# Esquem_tico_TP1_ASSD.net
KiCad netlist of a schematic drawn in Altium Designer
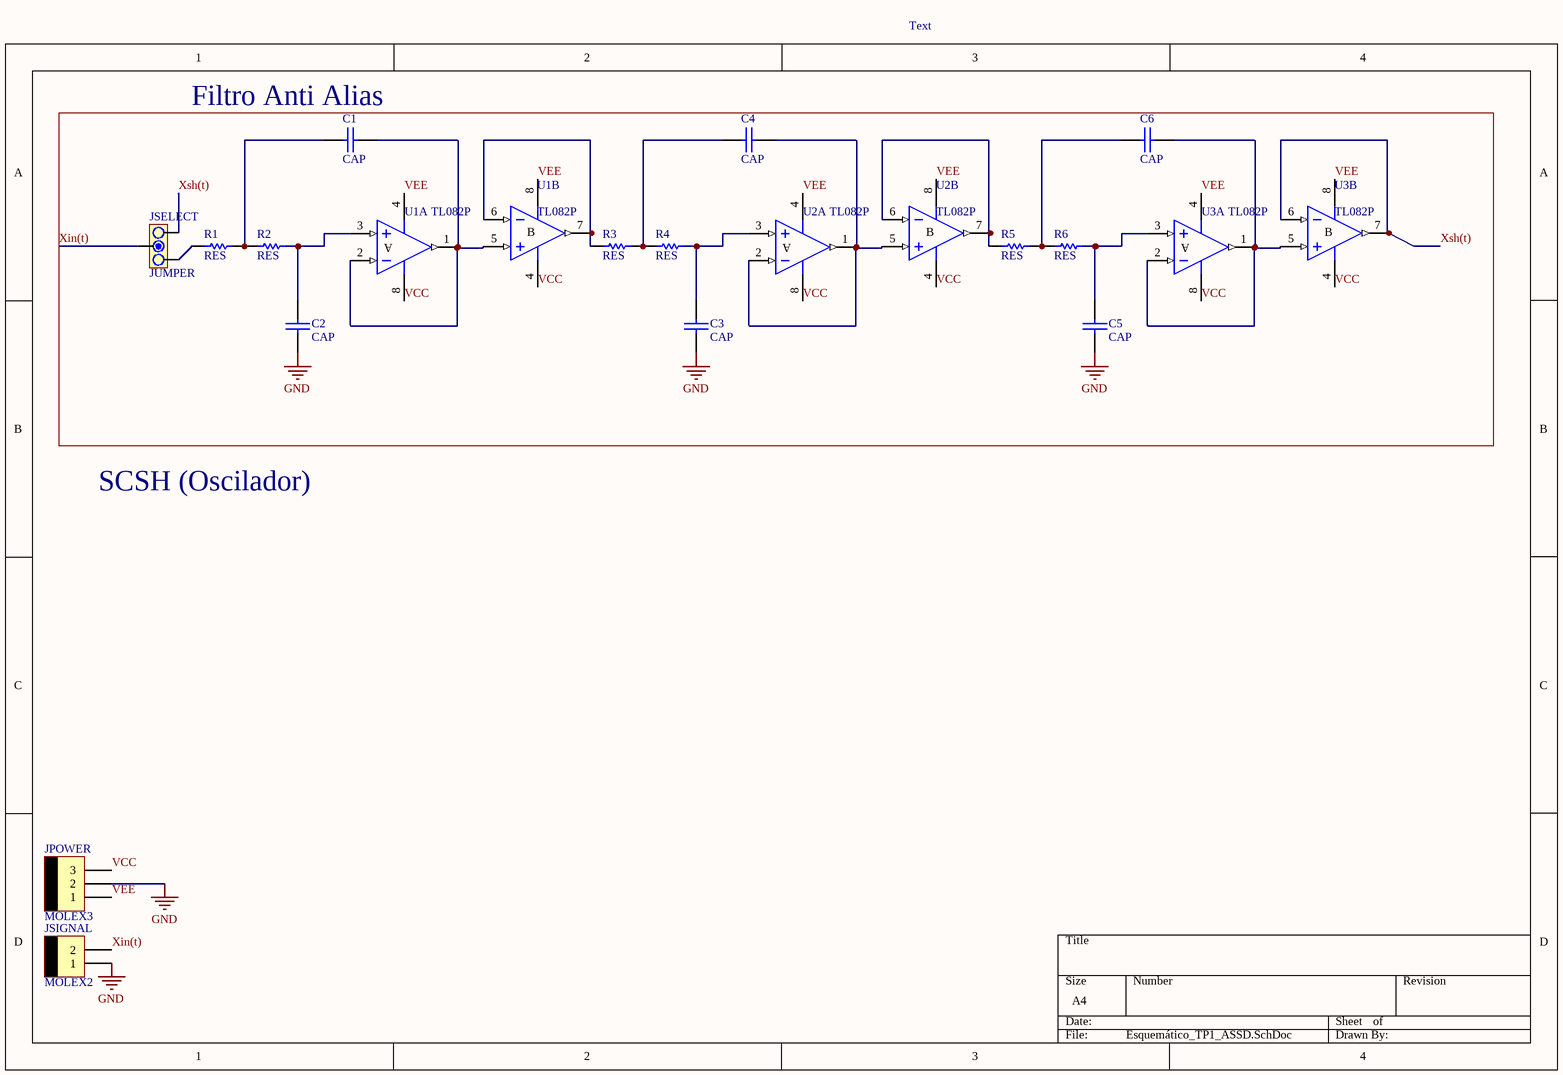
[diagram p0: Esquemático_TP1_ASSD.SchDoc]

(export (version "E")
  (design (tool "Eeschema 10.0.6"))
  (components
    (comp (ref "C1") (value "CAP") (footprint "CAP200") (libsource (lib "LIB PIO IX") (part "CAP")))
    (comp (ref "C2") (value "CAP") (footprint "CAP200") (libsource (lib "LIB PIO IX") (part "CAP")))
    (comp (ref "C3") (value "CAP") (footprint "CAP200") (libsource (lib "LIB PIO IX") (part "CAP")))
    (comp (ref "C4") (value "CAP") (footprint "CAP200") (libsource (lib "LIB PIO IX") (part "CAP")))
    (comp (ref "C5") (value "CAP") (footprint "CAP200") (libsource (lib "LIB PIO IX") (part "CAP")))
    (comp (ref "C6") (value "CAP") (footprint "CAP200") (libsource (lib "LIB PIO IX") (part "CAP")))
    (comp (ref "JPOWER") (value "MOLEX3") (footprint "MOLEX3") (libsource (lib "LIB PIO IX") (part "MOLEX3")))
    (comp (ref "JSELECT")
      (value "JUMPER")
      (footprint "JUMPER3")
      (libsource (lib "LIB PIO IX") (part "JUMPER3"))
    )
    (comp (ref "JSIGNAL")
      (value "MOLEX2")
      (footprint "MOLEX2")
      (libsource (lib "LIB PIO IX") (part "MOLEX2"))
    )
    (comp (ref "R1") (value "RES") (footprint "RES400") (libsource (lib "LIB PIO IX") (part "RES")))
    (comp (ref "R2") (value "RES") (footprint "RES400") (libsource (lib "LIB PIO IX") (part "RES")))
    (comp (ref "R3") (value "RES") (footprint "RES400") (libsource (lib "LIB PIO IX") (part "RES")))
    (comp (ref "R4") (value "RES") (footprint "RES400") (libsource (lib "LIB PIO IX") (part "RES")))
    (comp (ref "R5") (value "RES") (footprint "RES400") (libsource (lib "LIB PIO IX") (part "RES")))
    (comp (ref "R6") (value "RES") (footprint "RES400") (libsource (lib "LIB PIO IX") (part "RES")))
    (comp (ref "U1")
      (value "TL082P")
      (footprint "P008")
      (description "JFET-Input Operational Amplifier")
      (fields (field (name "PUBLISHER") "Altium Limited"))
      (libsource (lib "TI Operational Amplifier") (part "TL082P"))
    )
    (comp (ref "U2")
      (value "TL082P")
      (footprint "P008")
      (description "JFET-Input Operational Amplifier")
      (fields (field (name "PUBLISHER") "Altium Limited"))
      (libsource (lib "TI Operational Amplifier") (part "TL082P"))
    )
    (comp (ref "U3")
      (value "TL082P")
      (footprint "P008")
      (description "JFET-Input Operational Amplifier")
      (fields (field (name "PUBLISHER") "Altium Limited"))
      (libsource (lib "TI Operational Amplifier") (part "TL082P"))
    )
  )
  (nets
    (net (code "1") (name "/VCC") (class "Default")
      (node (ref "JPOWER") (pin "3") (pinfunction "3_3") (pintype "passive"))
      (node (ref "U1") (pin "4") (pinfunction "V-_4") (pintype "power_in"))
      (node (ref "U1") (pin "8") (pinfunction "V+_8") (pintype "power_in"))
      (node (ref "U2") (pin "4") (pinfunction "V-_4") (pintype "power_in"))
      (node (ref "U2") (pin "8") (pinfunction "V+_8") (pintype "power_in"))
      (node (ref "U3") (pin "4") (pinfunction "V-_4") (pintype "power_in"))
      (node (ref "U3") (pin "8") (pinfunction "V+_8") (pintype "power_in"))
    )
    (net (code "2") (name "/VEE") (class "Default")
      (node (ref "JPOWER") (pin "1") (pinfunction "1_1") (pintype "passive"))
      (node (ref "U1") (pin "4") (pinfunction "V-_4") (pintype "power_in"))
      (node (ref "U1") (pin "8") (pinfunction "V+_8") (pintype "power_in"))
      (node (ref "U2") (pin "4") (pinfunction "V-_4") (pintype "power_in"))
      (node (ref "U2") (pin "8") (pinfunction "V+_8") (pintype "power_in"))
      (node (ref "U3") (pin "4") (pinfunction "V-_4") (pintype "power_in"))
      (node (ref "U3") (pin "8") (pinfunction "V+_8") (pintype "power_in"))
    )
    (net (code "3") (name "/Xin(t)") (class "Default")
      (node (ref "JSELECT") (pin "2") (pinfunction "2_2") (pintype "passive"))
      (node (ref "JSIGNAL") (pin "2") (pinfunction "2_2") (pintype "passive"))
    )
    (net (code "4") (name "/Xsh(t)") (class "Default")
      (node (ref "JSELECT") (pin "1") (pinfunction "1_1") (pintype "passive"))
      (node (ref "U3") (pin "6") (pinfunction "IN-_6") (pintype "input"))
      (node (ref "U3") (pin "7") (pinfunction "OUT_7") (pintype "output"))
    )
    (net (code "5") (name "GND") (class "Default")
      (node (ref "C2") (pin "2") (pinfunction "2_2") (pintype "passive"))
      (node (ref "C3") (pin "2") (pinfunction "2_2") (pintype "passive"))
      (node (ref "C5") (pin "2") (pinfunction "2_2") (pintype "passive"))
      (node (ref "JPOWER") (pin "2") (pinfunction "2_2") (pintype "passive"))
      (node (ref "JSIGNAL") (pin "1") (pinfunction "1_1") (pintype "passive"))
    )
    (net (code "6") (name "Net-(C1-Pad1)") (class "Default")
      (node (ref "C1") (pin "1") (pinfunction "1_1") (pintype "passive"))
      (node (ref "R1") (pin "2") (pinfunction "2_2") (pintype "passive"))
      (node (ref "R2") (pin "1") (pinfunction "1_1") (pintype "passive"))
    )
    (net (code "7") (name "Net-(C4-Pad1)") (class "Default")
      (node (ref "C4") (pin "1") (pinfunction "1_1") (pintype "passive"))
      (node (ref "R3") (pin "2") (pinfunction "2_2") (pintype "passive"))
      (node (ref "R4") (pin "1") (pinfunction "1_1") (pintype "passive"))
    )
    (net (code "8") (name "Net-(C6-Pad1)") (class "Default")
      (node (ref "C6") (pin "1") (pinfunction "1_1") (pintype "passive"))
      (node (ref "R5") (pin "2") (pinfunction "2_2") (pintype "passive"))
      (node (ref "R6") (pin "1") (pinfunction "1_1") (pintype "passive"))
    )
    (net (code "9") (name "Net-(JSELECT-Pad3)") (class "Default")
      (node (ref "JSELECT") (pin "3") (pinfunction "3_3") (pintype "passive"))
      (node (ref "R1") (pin "1") (pinfunction "1_1") (pintype "passive"))
    )
    (net (code "10") (name "Net-(U1A-IN+)") (class "Default")
      (node (ref "C2") (pin "1") (pinfunction "1_1") (pintype "passive"))
      (node (ref "R2") (pin "2") (pinfunction "2_2") (pintype "passive"))
      (node (ref "U1") (pin "3") (pinfunction "IN+_3") (pintype "input"))
    )
    (net (code "11") (name "Net-(U1A-IN-)") (class "Default")
      (node (ref "C1") (pin "2") (pinfunction "2_2") (pintype "passive"))
      (node (ref "U1") (pin "1") (pinfunction "OUT_1") (pintype "output"))
      (node (ref "U1") (pin "2") (pinfunction "IN-_2") (pintype "input"))
      (node (ref "U1") (pin "5") (pinfunction "IN+_5") (pintype "input"))
    )
    (net (code "12") (name "Net-(U1B-IN-)") (class "Default")
      (node (ref "R3") (pin "1") (pinfunction "1_1") (pintype "passive"))
      (node (ref "U1") (pin "6") (pinfunction "IN-_6") (pintype "input"))
      (node (ref "U1") (pin "7") (pinfunction "OUT_7") (pintype "output"))
    )
    (net (code "13") (name "Net-(U2A-IN+)") (class "Default")
      (node (ref "C3") (pin "1") (pinfunction "1_1") (pintype "passive"))
      (node (ref "R4") (pin "2") (pinfunction "2_2") (pintype "passive"))
      (node (ref "U2") (pin "3") (pinfunction "IN+_3") (pintype "input"))
    )
    (net (code "14") (name "Net-(U2A-IN-)") (class "Default")
      (node (ref "C4") (pin "2") (pinfunction "2_2") (pintype "passive"))
      (node (ref "U2") (pin "1") (pinfunction "OUT_1") (pintype "output"))
      (node (ref "U2") (pin "2") (pinfunction "IN-_2") (pintype "input"))
      (node (ref "U2") (pin "5") (pinfunction "IN+_5") (pintype "input"))
    )
    (net (code "15") (name "Net-(U2B-IN-)") (class "Default")
      (node (ref "R5") (pin "1") (pinfunction "1_1") (pintype "passive"))
      (node (ref "U2") (pin "6") (pinfunction "IN-_6") (pintype "input"))
      (node (ref "U2") (pin "7") (pinfunction "OUT_7") (pintype "output"))
    )
    (net (code "16") (name "Net-(U3A-IN+)") (class "Default")
      (node (ref "C5") (pin "1") (pinfunction "1_1") (pintype "passive"))
      (node (ref "R6") (pin "2") (pinfunction "2_2") (pintype "passive"))
      (node (ref "U3") (pin "3") (pinfunction "IN+_3") (pintype "input"))
    )
    (net (code "17") (name "Net-(U3A-IN-)") (class "Default")
      (node (ref "C6") (pin "2") (pinfunction "2_2") (pintype "passive"))
      (node (ref "U3") (pin "1") (pinfunction "OUT_1") (pintype "output"))
      (node (ref "U3") (pin "2") (pinfunction "IN-_2") (pintype "input"))
      (node (ref "U3") (pin "5") (pinfunction "IN+_5") (pintype "input"))
    )
  )
)
